# Sensors.net
KiCad netlist of a schematic drawn in Altium Designer
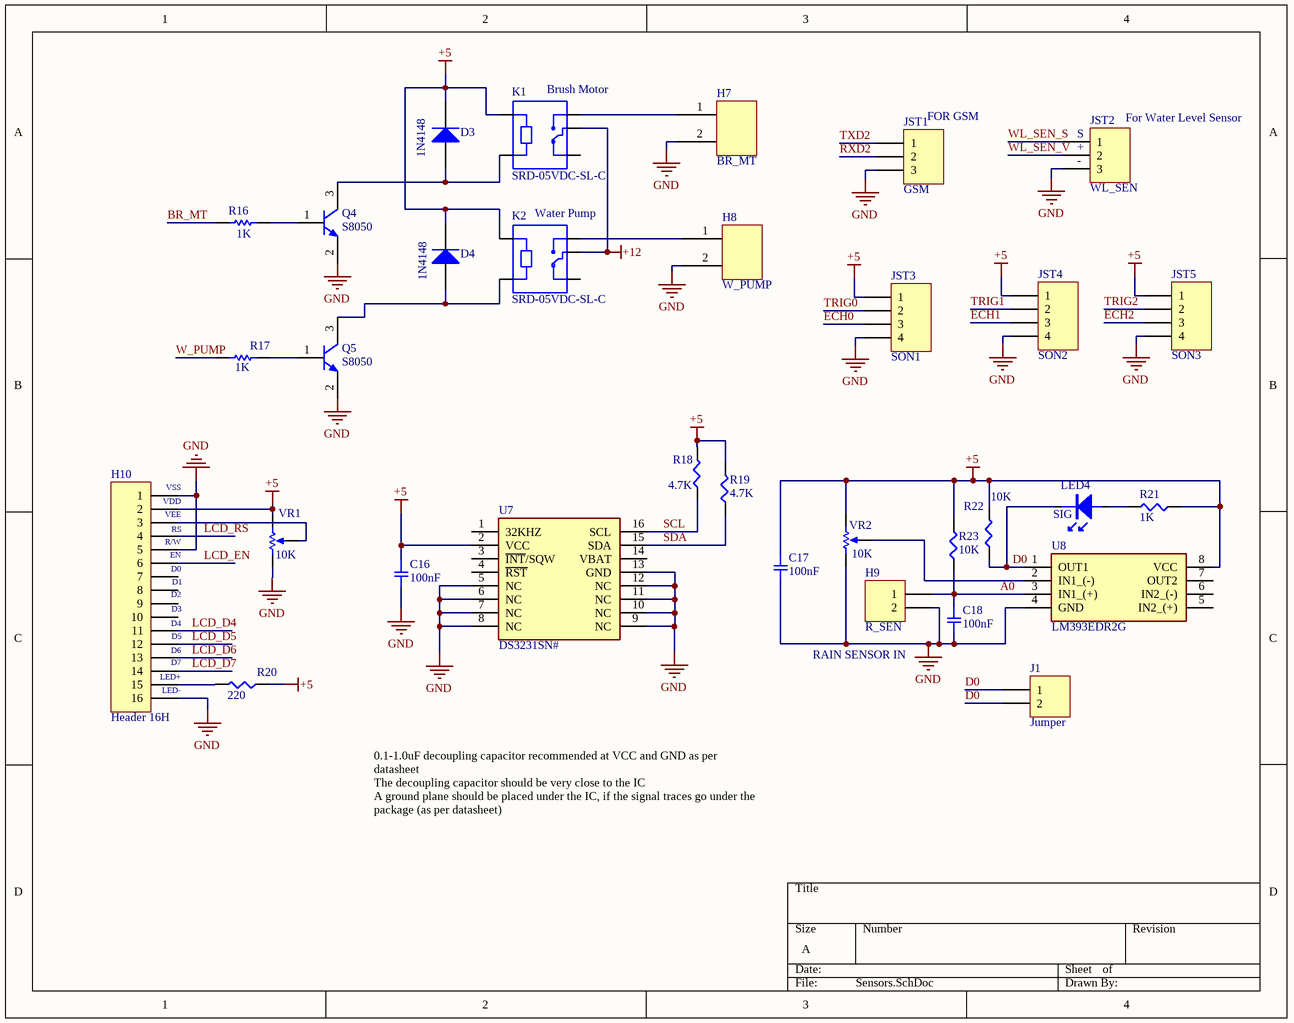
[diagram p0: Sensors.SchDoc]

(export (version "E")
  (design (tool "Eeschema 10.0.6"))
  (components
    (comp (ref "C16")
      (value "100nF")
      (footprint "SMD-0805C")
      (description "CAP CER 10000PF 250V X7T 0805")
      (fields
        (field (name "DIGI-KEY PART NUMBER") "490-13986-1-ND")
        (field (name "PART NUMBER") "GC321AD72E103KX01D")
      )
      (libsource (lib "capacitor0805") (part "GC321AD72E103KX01D"))
    )
    (comp (ref "C17")
      (value "100nF")
      (footprint "SMD-0805C")
      (description "CAP CER 10000PF 250V X7T 0805")
      (fields
        (field (name "DIGI-KEY PART NUMBER") "490-13986-1-ND")
        (field (name "PART NUMBER") "GC321AD72E103KX01D")
      )
      (libsource (lib "capacitor0805") (part "GC321AD72E103KX01D"))
    )
    (comp (ref "C18")
      (value "100nF")
      (footprint "SMD-0805C")
      (description "CAP CER 10000PF 250V X7T 0805")
      (fields
        (field (name "DIGI-KEY PART NUMBER") "490-13986-1-ND")
        (field (name "PART NUMBER") "GC321AD72E103KX01D")
      )
      (libsource (lib "capacitor0805") (part "GC321AD72E103KX01D"))
    )
    (comp (ref "D3")
      (value "1N4148")
      (footprint "LL4148-L3.7 SMD(LCSC)")
      (description "High Conductance Fast Diode")
      (fields (field (name "PUBLISHER") "Altium Limited"))
      (libsource (lib "Miscellaneous Devices") (part "Diode 1N4148"))
    )
    (comp (ref "D4")
      (value "1N4148")
      (footprint "LL4148-L3.7 SMD(LCSC)")
      (description "High Conductance Fast Diode")
      (fields (field (name "PUBLISHER") "Altium Limited"))
      (libsource (lib "Miscellaneous Devices") (part "Diode 1N4148"))
    )
    (comp (ref "H7")
      (value "BR_MT")
      (footprint "Header_I2")
      (description "2-pin single line header (in Blue/green color) Normal")
      (libsource (lib "Header_I2") (part "Header_I2"))
    )
    (comp (ref "H8")
      (value "W_PUMP")
      (footprint "Header_I2")
      (description "2-pin single line header (in Blue/green color) Normal")
      (libsource (lib "Header_I2") (part "Header_I2"))
    )
    (comp (ref "H9")
      (value "R_SEN")
      (footprint "HDR1X2")
      (description "Header, 2-Pin")
      (fields (field (name "PUBLISHER") "Altium Limited"))
      (libsource (lib "Miscellaneous Connectors") (part "Header 2"))
    )
    (comp (ref "H10")
      (value "Header 16H")
      (footprint "HDR1X16H")
      (description "Header, 16-Pin, Right Angle")
      (fields (field (name "PUBLISHER") "Altium Limited"))
      (libsource (lib "Miscellaneous Connectors") (part "Header 16H"))
    )
    (comp (ref "J1")
      (value "Jumper")
      (footprint "HDR1X2")
      (description "Header, 2-Pin")
      (fields (field (name "PUBLISHER") "Altium Limited"))
      (libsource (lib "") (part "Header 2_1"))
    )
    (comp (ref "JST1")
      (value "GSM")
      (footprint "HDR1X3")
      (description "Header, 3-Pin")
      (fields (field (name "PUBLISHER") "Altium Limited"))
      (libsource (lib "Miscellaneous Connectors") (part "Header 3"))
    )
    (comp (ref "JST2")
      (value "WL_SEN")
      (footprint "HDR1X3")
      (description "Header, 3-Pin")
      (fields (field (name "PUBLISHER") "Altium Limited"))
      (libsource (lib "Miscellaneous Connectors") (part "Header 3"))
    )
    (comp (ref "JST3")
      (value "SON1")
      (footprint "HDR1X4")
      (description "Header, 4-Pin")
      (fields (field (name "PUBLISHER") "Altium Limited"))
      (libsource (lib "Miscellaneous Connectors") (part "Header 4"))
    )
    (comp (ref "JST4")
      (value "SON2")
      (footprint "HDR1X4")
      (description "Header, 4-Pin")
      (fields (field (name "PUBLISHER") "Altium Limited"))
      (libsource (lib "Miscellaneous Connectors") (part "Header 4"))
    )
    (comp (ref "JST5")
      (value "SON3")
      (footprint "HDR1X4")
      (description "Header, 4-Pin")
      (fields (field (name "PUBLISHER") "Altium Limited"))
      (libsource (lib "Miscellaneous Connectors") (part "Header 4"))
    )
    (comp (ref "K1")
      (value "SRD-05VDC-SL-C")
      (footprint "SRD-05VDC-SL-C")
      (fields (field (name "MF") "Songle Relay"))
      (libsource (lib "SRD-05VDC-SL-C") (part "SRD-05VDC-SL-C"))
    )
    (comp (ref "K2")
      (value "SRD-05VDC-SL-C")
      (footprint "SRD-05VDC-SL-C")
      (fields (field (name "MF") "Songle Relay"))
      (libsource (lib "SRD-05VDC-SL-C") (part "SRD-05VDC-SL-C"))
    )
    (comp (ref "LED4")
      (value "SIG")
      (footprint "RED_LED_0805")
      (description "SMT LED")
      (libsource (lib "SMT-LED") (part "LED 5V"))
    )
    (comp (ref "Q4")
      (value "S8050")
      (footprint "SMT_TRIODE_NPN")
      (description "S8050 NPN Bipolar Junction Transistor")
      (fields (field (name "PUBLISHER") "Altium Limited"))
      (libsource (lib "S8050") (part "S8050"))
    )
    (comp (ref "Q5")
      (value "S8050")
      (footprint "SMT_TRIODE_NPN")
      (description "S8050 NPN Bipolar Junction Transistor")
      (fields (field (name "PUBLISHER") "Altium Limited"))
      (libsource (lib "S8050") (part "S8050"))
    )
    (comp (ref "R16")
      (value "1K")
      (footprint "SMD-0805-RES")
      (description "Resistor")
      (fields (field (name "PUBLISHER") "Altium Limited"))
      (libsource (lib "Miscellaneous Devices") (part "Res1"))
    )
    (comp (ref "R17")
      (value "1K")
      (footprint "SMD-0805-RES")
      (description "Resistor")
      (fields (field (name "PUBLISHER") "Altium Limited"))
      (libsource (lib "Miscellaneous Devices") (part "Res1"))
    )
    (comp (ref "R18")
      (value "4.7K")
      (footprint "SMD-0805-RES")
      (description "RES SMD 1 OHM 1% 1/3W 0805")
      (fields (field (name "PART NUMBER") "ERJ-6BQF1R0V") (field (name "DIGI-KEY PART NUMBER") "P17499CT-ND"))
      (libsource (lib "Res0805") (part "ERJ-6BQF1R0V"))
    )
    (comp (ref "R19")
      (value "4.7K")
      (footprint "SMD-0805-RES")
      (description "RES SMD 1 OHM 1% 1/3W 0805")
      (fields (field (name "PART NUMBER") "ERJ-6BQF1R0V") (field (name "DIGI-KEY PART NUMBER") "P17499CT-ND"))
      (libsource (lib "Res0805") (part "ERJ-6BQF1R0V"))
    )
    (comp (ref "R20")
      (value "220")
      (footprint "SMD-0805-RES")
      (description "RES SMD 1 OHM 1% 1/3W 0805")
      (fields (field (name "PART NUMBER") "ERJ-6BQF1R0V") (field (name "DIGI-KEY PART NUMBER") "P17499CT-ND"))
      (libsource (lib "Res0805") (part "ERJ-6BQF1R0V"))
    )
    (comp (ref "R21")
      (value "1K")
      (footprint "SMD-0805-RES")
      (description "RES SMD 1 OHM 1% 1/3W 0805")
      (fields (field (name "PART NUMBER") "ERJ-6BQF1R0V") (field (name "DIGI-KEY PART NUMBER") "P17499CT-ND"))
      (libsource (lib "Res0805") (part "ERJ-6BQF1R0V"))
    )
    (comp (ref "R22")
      (value "10K")
      (footprint "SMD-0805-RES")
      (description "RES SMD 1 OHM 1% 1/3W 0805")
      (fields (field (name "PART NUMBER") "ERJ-6BQF1R0V") (field (name "DIGI-KEY PART NUMBER") "P17499CT-ND"))
      (libsource (lib "Res0805") (part "ERJ-6BQF1R0V"))
    )
    (comp (ref "R23")
      (value "10K")
      (footprint "SMD-0805-RES")
      (description "RES SMD 1 OHM 1% 1/3W 0805")
      (fields (field (name "PART NUMBER") "ERJ-6BQF1R0V") (field (name "DIGI-KEY PART NUMBER") "P17499CT-ND"))
      (libsource (lib "Res0805") (part "ERJ-6BQF1R0V"))
    )
    (comp (ref "U7")
      (value "DS3231SN#")
      (footprint "DS3231(Module-footprint)")
      (description "Real Time Clock IC")
      (fields (field (name "MOUSER PART NUMBER") "700-DS3231SN#") (field (name "RS PART NUMBER") "1897251"))
      (libsource (lib "DS3231") (part "DS3231SN#"))
    )
    (comp (ref "U8")
      (value "LM393EDR2G")
      (footprint "SOIC-8")
      (description "Integrated Circuit")
      (fields
        (field (name "MANUFACTURER_PART_NUMBER") "LM358N")
        (field (name "MOUSER PART NUMBER") "512-LM358N")
      )
      (libsource (lib "LM358") (part "LM358N"))
    )
    (comp (ref "VR1")
      (value "10K")
      (footprint "VR7(LCSC)")
      (description "Potentiometer")
      (fields (field (name "Comment") "10K potentiometer") (field (name "PUBLISHER") "Altium Limited"))
      (libsource (lib "") (part "RPot_1"))
    )
    (comp (ref "VR2")
      (value "10K")
      (footprint "VR7(LCSC)")
      (description "Potentiometer")
      (fields (field (name "Comment") "10K potentiometer") (field (name "PUBLISHER") "Altium Limited"))
      (libsource (lib "Miscellaneous Devices") (part "RPot"))
    )
  )
  (nets
    (net (code "1") (name "+5") (class "Default")
      (node (ref "C16") (pin "1") (pinfunction "1_1") (pintype "passive"))
      (node (ref "C17") (pin "1") (pinfunction "1_1") (pintype "passive"))
      (node (ref "D3") (pin "2") (pinfunction "K_2") (pintype "passive"))
      (node (ref "D4") (pin "2") (pinfunction "K_2") (pintype "passive"))
      (node (ref "H10") (pin "2") (pinfunction "2_2") (pintype "passive"))
      (node (ref "JST3") (pin "1") (pinfunction "1_1") (pintype "passive"))
      (node (ref "JST4") (pin "1") (pinfunction "1_1") (pintype "passive"))
      (node (ref "JST5") (pin "1") (pinfunction "1_1") (pintype "passive"))
      (node (ref "K1") (pin "A1") (pinfunction "A1_A1") (pintype "passive"))
      (node (ref "K2") (pin "A1") (pinfunction "A1_A1") (pintype "passive"))
      (node (ref "R18") (pin "2") (pinfunction "2_2") (pintype "passive"))
      (node (ref "R19") (pin "2") (pinfunction "2_2") (pintype "passive"))
      (node (ref "R20") (pin "1") (pinfunction "1_1") (pintype "passive"))
      (node (ref "R21") (pin "1") (pinfunction "1_1") (pintype "passive"))
      (node (ref "R22") (pin "2") (pinfunction "2_2") (pintype "passive"))
      (node (ref "R23") (pin "2") (pinfunction "2_2") (pintype "passive"))
      (node (ref "U7") (pin "2") (pinfunction "VCC_2") (pintype "power_in"))
      (node (ref "U8") (pin "8") (pinfunction "VCC_8") (pintype "passive"))
      (node (ref "VR1") (pin "3") (pinfunction "TOP_3") (pintype "passive"))
      (node (ref "VR2") (pin "3") (pinfunction "TOP_3") (pintype "passive"))
    )
    (net (code "2") (name "+12") (class "Default")
      (node (ref "K1") (pin "COM") (pinfunction "COM_COM") (pintype "passive"))
      (node (ref "K2") (pin "COM") (pinfunction "COM_COM") (pintype "passive"))
    )
    (net (code "3") (name "/A0") (class "Default")
      (node (ref "C18") (pin "1") (pinfunction "1_1") (pintype "passive"))
      (node (ref "H9") (pin "1") (pinfunction "1_1") (pintype "passive"))
      (node (ref "R23") (pin "1") (pinfunction "1_1") (pintype "passive"))
      (node (ref "U8") (pin "3") (pinfunction "IN1_(+)_3") (pintype "passive"))
    )
    (net (code "4") (name "/BR_MT") (class "Default")
      (node (ref "R16") (pin "1") (pinfunction "1_1") (pintype "passive"))
    )
    (net (code "5") (name "/D0") (class "Default")
      (node (ref "J1") (pin "1") (pinfunction "1_1") (pintype "passive"))
      (node (ref "J1") (pin "2") (pinfunction "2_2") (pintype "passive"))
      (node (ref "LED4") (pin "2") (pinfunction "K_2") (pintype "passive"))
      (node (ref "R22") (pin "1") (pinfunction "1_1") (pintype "passive"))
      (node (ref "U8") (pin "1") (pinfunction "OUT1_1") (pintype "passive"))
    )
    (net (code "6") (name "/ECH0") (class "Default")
      (node (ref "JST3") (pin "3") (pinfunction "3_3") (pintype "passive"))
    )
    (net (code "7") (name "/ECH1") (class "Default")
      (node (ref "JST4") (pin "3") (pinfunction "3_3") (pintype "passive"))
    )
    (net (code "8") (name "/ECH2") (class "Default")
      (node (ref "JST5") (pin "3") (pinfunction "3_3") (pintype "passive"))
    )
    (net (code "9") (name "/LCD_D4") (class "Default")
      (node (ref "H10") (pin "11") (pinfunction "11_11") (pintype "passive"))
    )
    (net (code "10") (name "/LCD_D5") (class "Default")
      (node (ref "H10") (pin "12") (pinfunction "12_12") (pintype "passive"))
    )
    (net (code "11") (name "/LCD_D6") (class "Default")
      (node (ref "H10") (pin "13") (pinfunction "13_13") (pintype "passive"))
    )
    (net (code "12") (name "/LCD_D7") (class "Default")
      (node (ref "H10") (pin "14") (pinfunction "14_14") (pintype "passive"))
    )
    (net (code "13") (name "/LCD_EN") (class "Default")
      (node (ref "H10") (pin "6") (pinfunction "6_6") (pintype "passive"))
    )
    (net (code "14") (name "/LCD_RS") (class "Default")
      (node (ref "H10") (pin "4") (pinfunction "4_4") (pintype "passive"))
    )
    (net (code "15") (name "/RXD2") (class "Default")
      (node (ref "JST1") (pin "2") (pinfunction "2_2") (pintype "passive"))
    )
    (net (code "16") (name "/SCL") (class "Default")
      (node (ref "R18") (pin "1") (pinfunction "1_1") (pintype "passive"))
      (node (ref "U7") (pin "16") (pinfunction "SCL_16") (pintype "passive"))
    )
    (net (code "17") (name "/SDA") (class "Default")
      (node (ref "R19") (pin "1") (pinfunction "1_1") (pintype "passive"))
      (node (ref "U7") (pin "15") (pinfunction "SDA_15") (pintype "passive"))
    )
    (net (code "18") (name "/TRIG0") (class "Default")
      (node (ref "JST3") (pin "2") (pinfunction "2_2") (pintype "passive"))
    )
    (net (code "19") (name "/TRIG1") (class "Default")
      (node (ref "JST4") (pin "2") (pinfunction "2_2") (pintype "passive"))
    )
    (net (code "20") (name "/TRIG2") (class "Default")
      (node (ref "JST5") (pin "2") (pinfunction "2_2") (pintype "passive"))
    )
    (net (code "21") (name "/TXD2") (class "Default")
      (node (ref "JST1") (pin "1") (pinfunction "1_1") (pintype "passive"))
    )
    (net (code "22") (name "/WL_SEN_S") (class "Default")
      (node (ref "JST2") (pin "1") (pinfunction "1_1") (pintype "passive"))
    )
    (net (code "23") (name "/WL_SEN_V") (class "Default")
      (node (ref "JST2") (pin "2") (pinfunction "2_2") (pintype "passive"))
    )
    (net (code "24") (name "/W_PUMP") (class "Default")
      (node (ref "R17") (pin "1") (pinfunction "1_1") (pintype "passive"))
    )
    (net (code "25") (name "GND") (class "Default")
      (node (ref "C16") (pin "2") (pinfunction "2_2") (pintype "passive"))
      (node (ref "C17") (pin "2") (pinfunction "2_2") (pintype "passive"))
      (node (ref "C18") (pin "2") (pinfunction "2_2") (pintype "passive"))
      (node (ref "H10") (pin "1") (pinfunction "1_1") (pintype "passive"))
      (node (ref "H10") (pin "16") (pinfunction "16_16") (pintype "passive"))
      (node (ref "H10") (pin "5") (pinfunction "5_5") (pintype "passive"))
      (node (ref "H7") (pin "2") (pintype "passive"))
      (node (ref "H8") (pin "2") (pintype "passive"))
      (node (ref "H9") (pin "2") (pinfunction "2_2") (pintype "passive"))
      (node (ref "JST1") (pin "3") (pinfunction "3_3") (pintype "passive"))
      (node (ref "JST2") (pin "3") (pinfunction "3_3") (pintype "passive"))
      (node (ref "JST3") (pin "4") (pinfunction "4_4") (pintype "passive"))
      (node (ref "JST4") (pin "4") (pinfunction "4_4") (pintype "passive"))
      (node (ref "JST5") (pin "4") (pinfunction "4_4") (pintype "passive"))
      (node (ref "Q4") (pin "2") (pinfunction "E_2") (pintype "passive"))
      (node (ref "Q5") (pin "2") (pinfunction "E_2") (pintype "passive"))
      (node (ref "U7") (pin "10") (pinfunction "NC_10") (pintype "passive"))
      (node (ref "U7") (pin "11") (pinfunction "NC_11") (pintype "passive"))
      (node (ref "U7") (pin "12") (pinfunction "NC_12") (pintype "passive"))
      (node (ref "U7") (pin "13") (pinfunction "GND_13") (pintype "power_in"))
      (node (ref "U7") (pin "5") (pinfunction "NC_5") (pintype "passive"))
      (node (ref "U7") (pin "6") (pinfunction "NC_6") (pintype "passive"))
      (node (ref "U7") (pin "7") (pinfunction "NC_7") (pintype "passive"))
      (node (ref "U7") (pin "8") (pinfunction "NC_8") (pintype "passive"))
      (node (ref "U7") (pin "9") (pinfunction "NC_9") (pintype "passive"))
      (node (ref "U8") (pin "4") (pinfunction "GND_4") (pintype "passive"))
      (node (ref "VR1") (pin "1") (pinfunction "BOT_1") (pintype "passive"))
      (node (ref "VR2") (pin "1") (pinfunction "BOT_1") (pintype "passive"))
    )
    (net (code "26") (name "Net-(D3-A)") (class "Default")
      (node (ref "D3") (pin "1") (pinfunction "A_1") (pintype "passive"))
      (node (ref "K1") (pin "A2") (pinfunction "A2_A2") (pintype "passive"))
      (node (ref "Q4") (pin "3") (pinfunction "C_3") (pintype "passive"))
    )
    (net (code "27") (name "Net-(D4-A)") (class "Default")
      (node (ref "D4") (pin "1") (pinfunction "A_1") (pintype "passive"))
      (node (ref "K2") (pin "A2") (pinfunction "A2_A2") (pintype "passive"))
      (node (ref "Q5") (pin "3") (pinfunction "C_3") (pintype "passive"))
    )
    (net (code "28") (name "Net-(H7-Pad1)") (class "Default")
      (node (ref "H7") (pin "1") (pintype "passive"))
      (node (ref "K1") (pin "NO") (pinfunction "NO_NO") (pintype "passive"))
    )
    (net (code "29") (name "Net-(H8-Pad1)") (class "Default")
      (node (ref "H8") (pin "1") (pintype "passive"))
      (node (ref "K2") (pin "NO") (pinfunction "NO_NO") (pintype "passive"))
    )
    (net (code "30") (name "Net-(H10-Pad15)") (class "Default")
      (node (ref "H10") (pin "15") (pinfunction "15_15") (pintype "passive"))
      (node (ref "R20") (pin "2") (pinfunction "2_2") (pintype "passive"))
    )
    (net (code "31") (name "Net-(LED4-A)") (class "Default")
      (node (ref "LED4") (pin "1") (pinfunction "A_1") (pintype "passive"))
      (node (ref "R21") (pin "2") (pinfunction "2_2") (pintype "passive"))
    )
    (net (code "32") (name "Net-(Q4-B)") (class "Default")
      (node (ref "Q4") (pin "1") (pinfunction "B_1") (pintype "passive"))
      (node (ref "R16") (pin "2") (pinfunction "2_2") (pintype "passive"))
    )
    (net (code "33") (name "Net-(Q5-B)") (class "Default")
      (node (ref "Q5") (pin "1") (pinfunction "B_1") (pintype "passive"))
      (node (ref "R17") (pin "2") (pinfunction "2_2") (pintype "passive"))
    )
    (net (code "34") (name "Net-(U8-IN1_(-))") (class "Default")
      (node (ref "U8") (pin "2") (pinfunction "IN1_(-)_2") (pintype "passive"))
      (node (ref "VR2") (pin "2") (pinfunction "TAP_2") (pintype "passive"))
    )
    (net (code "35") (name "Net-(VR1-TAP)") (class "Default")
      (node (ref "H10") (pin "3") (pinfunction "3_3") (pintype "passive"))
      (node (ref "VR1") (pin "2") (pinfunction "TAP_2") (pintype "passive"))
    )
    (net (code "36") (name "unconnected-(H10-Pad7)") (class "Default")
      (node (ref "H10") (pin "7") (pinfunction "7_7") (pintype "passive"))
    )
    (net (code "37") (name "unconnected-(H10-Pad8)") (class "Default")
      (node (ref "H10") (pin "8") (pinfunction "8_8") (pintype "passive"))
    )
    (net (code "38") (name "unconnected-(H10-Pad9)") (class "Default")
      (node (ref "H10") (pin "9") (pinfunction "9_9") (pintype "passive"))
    )
    (net (code "39") (name "unconnected-(H10-Pad10)") (class "Default")
      (node (ref "H10") (pin "10") (pinfunction "10_10") (pintype "passive"))
    )
    (net (code "40") (name "unconnected-(K1-PadNC)") (class "Default")
      (node (ref "K1") (pin "NC") (pinfunction "NC_NC") (pintype "passive"))
    )
    (net (code "41") (name "unconnected-(K2-PadNC)") (class "Default")
      (node (ref "K2") (pin "NC") (pinfunction "NC_NC") (pintype "passive"))
    )
    (net (code "42") (name "unconnected-(U7-32KHZ-Pad1)") (class "Default")
      (node (ref "U7") (pin "1") (pinfunction "32KHZ_1") (pintype "passive"))
    )
    (net (code "43") (name "unconnected-(U7-VBAT-Pad14)") (class "Default")
      (node (ref "U7") (pin "14") (pinfunction "VBAT_14") (pintype "passive"))
    )
    (net (code "44") (name "unconnected-(U7-~{INT}{slash}SQW-Pad3)") (class "Default")
      (node (ref "U7") (pin "3") (pinfunction "~{INT}/SQW_3") (pintype "passive"))
    )
    (net (code "45") (name "unconnected-(U7-~{RST}-Pad4)") (class "Default")
      (node (ref "U7") (pin "4") (pinfunction "~{RST}_4") (pintype "passive"))
    )
    (net (code "46") (name "unconnected-(U8-IN2_(+)-Pad5)") (class "Default")
      (node (ref "U8") (pin "5") (pinfunction "IN2_(+)_5") (pintype "passive"))
    )
    (net (code "47") (name "unconnected-(U8-IN2_(-)-Pad6)") (class "Default")
      (node (ref "U8") (pin "6") (pinfunction "IN2_(-)_6") (pintype "passive"))
    )
    (net (code "48") (name "unconnected-(U8-OUT2-Pad7)") (class "Default")
      (node (ref "U8") (pin "7") (pinfunction "OUT2_7") (pintype "passive"))
    )
  )
)
